# filter.net
KiCad netlist of a schematic drawn in EAGLE
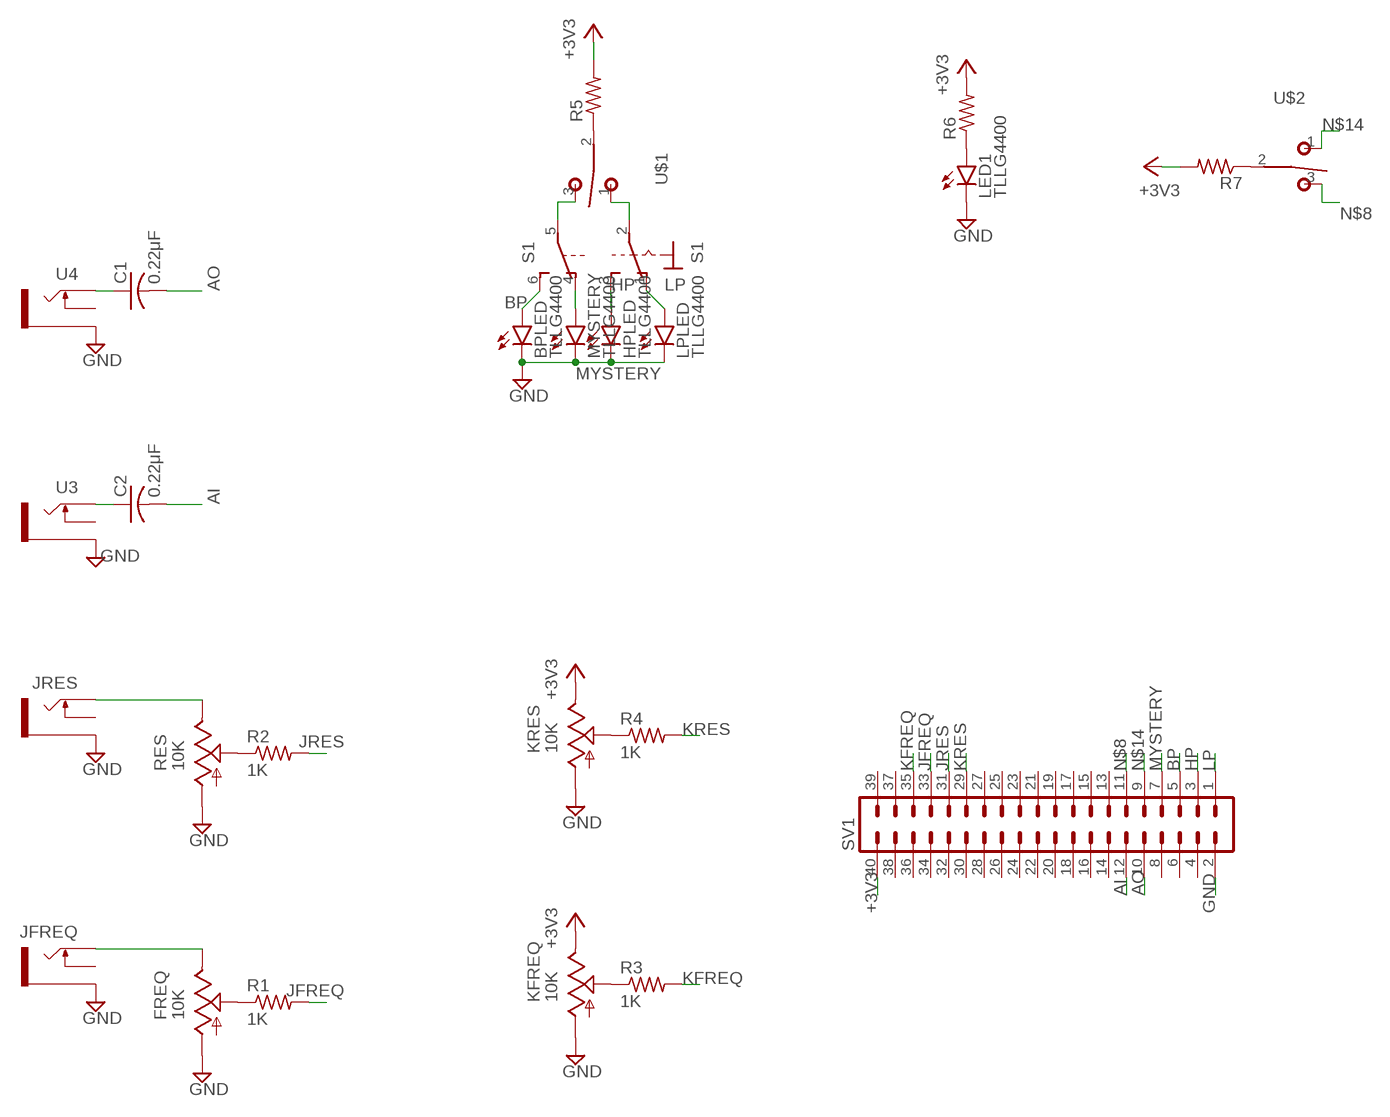
[diagram p0: schematic, sheet 1]

(export (version "E")
  (design (tool "Eeschema 10.0.6"))
  (components
    (comp (ref "BPLED")
      (value "TLLG4400")
      (footprint "eagle-import:LED3MM")
      (fields (field (name "MF") "VISHAY SEMICONDUCTOR"))
      (libsource (lib "eagle-import") (part "TLLG4400"))
    )
    (comp (ref "C1")
      (value "0.22μF")
      (footprint "eagle-import:C025-024X044")
      (libsource (lib "eagle-import") (part "C-US025-024X044"))
    )
    (comp (ref "C2")
      (value "0.22μF")
      (footprint "eagle-import:C025-024X044")
      (libsource (lib "eagle-import") (part "C-US025-024X044"))
    )
    (comp (ref "FREQ")
      (value "10K")
      (footprint "eagle-import:9MM_SNAP-IN_POT")
      (libsource (lib "eagle-import") (part "9MM_SNAP-IN_POT_"))
    )
    (comp (ref "HPLED")
      (value "TLLG4400")
      (footprint "eagle-import:LED3MM")
      (fields (field (name "MF") "VISHAY SEMICONDUCTOR"))
      (libsource (lib "eagle-import") (part "TLLG4400"))
    )
    (comp (ref "JFREQ")
      (value "THONKICONNNEW")
      (footprint "eagle-import:WQP-PJ301M-12_JACK")
      (libsource (lib "eagle-import") (part "THONKICONNNEW"))
    )
    (comp (ref "JRES")
      (value "THONKICONNNEW")
      (footprint "eagle-import:WQP-PJ301M-12_JACK")
      (libsource (lib "eagle-import") (part "THONKICONNNEW"))
    )
    (comp (ref "KFREQ")
      (value "10K")
      (footprint "eagle-import:9MM_SNAP-IN_POT")
      (libsource (lib "eagle-import") (part "9MM_SNAP-IN_POT_"))
    )
    (comp (ref "KRES")
      (value "10K")
      (footprint "eagle-import:9MM_SNAP-IN_POT")
      (libsource (lib "eagle-import") (part "9MM_SNAP-IN_POT_"))
    )
    (comp (ref "LED1")
      (value "TLLG4400")
      (footprint "eagle-import:LED3MM")
      (fields (field (name "MF") "VISHAY SEMICONDUCTOR"))
      (libsource (lib "eagle-import") (part "TLLG4400"))
    )
    (comp (ref "LPLED")
      (value "TLLG4400")
      (footprint "eagle-import:LED3MM")
      (fields (field (name "MF") "VISHAY SEMICONDUCTOR"))
      (libsource (lib "eagle-import") (part "TLLG4400"))
    )
    (comp (ref "MYSTERY")
      (value "TLLG4400")
      (footprint "eagle-import:LED3MM")
      (fields (field (name "MF") "VISHAY SEMICONDUCTOR"))
      (libsource (lib "eagle-import") (part "TLLG4400"))
    )
    (comp (ref "R1")
      (value "1K")
      (footprint "eagle-import:0207_10")
      (libsource (lib "eagle-import") (part "R-US_0207/10"))
    )
    (comp (ref "R2")
      (value "1K")
      (footprint "eagle-import:0207_10")
      (libsource (lib "eagle-import") (part "R-US_0207/10"))
    )
    (comp (ref "R3")
      (value "1K")
      (footprint "eagle-import:0207_10")
      (libsource (lib "eagle-import") (part "R-US_0207/10"))
    )
    (comp (ref "R4")
      (value "1K")
      (footprint "eagle-import:0207_10")
      (libsource (lib "eagle-import") (part "R-US_0207/10"))
    )
    (comp (ref "R5")
      (value "R-US_0207/10")
      (footprint "eagle-import:0207_10")
      (libsource (lib "eagle-import") (part "R-US_0207/10"))
    )
    (comp (ref "R6")
      (value "R-US_0207/10")
      (footprint "eagle-import:0207_10")
      (libsource (lib "eagle-import") (part "R-US_0207/10"))
    )
    (comp (ref "R7")
      (value "R-US_0207/10")
      (footprint "eagle-import:0207_10")
      (libsource (lib "eagle-import") (part "R-US_0207/10"))
    )
    (comp (ref "RES")
      (value "10K")
      (footprint "eagle-import:9MM_SNAP-IN_POT")
      (libsource (lib "eagle-import") (part "9MM_SNAP-IN_POT_"))
    )
    (comp (ref "S1")
      (value "320-938")
      (footprint "eagle-import:320-938")
      (libsource (lib "eagle-import") (part "320-938"))
    )
    (comp (ref "SV1")
      (value "MA20-2")
      (footprint "eagle-import:MA20-2")
      (libsource (lib "eagle-import") (part "MA20-2"))
    )
    (comp (ref "U$1")
      (value "T-80-T-SPDT-ON-OFF-ON")
      (footprint "eagle-import:M9040P")
      (libsource (lib "eagle-import") (part "T-80-T-SPDT-ON-OFF-ON"))
    )
    (comp (ref "U$2")
      (value "T-80-T-SPDT-ON-OFF-ON")
      (footprint "eagle-import:M9040P")
      (libsource (lib "eagle-import") (part "T-80-T-SPDT-ON-OFF-ON"))
    )
    (comp (ref "U3")
      (value "THONKICONNNEW")
      (footprint "eagle-import:WQP-PJ301M-12_JACK")
      (libsource (lib "eagle-import") (part "THONKICONNNEW"))
    )
    (comp (ref "U4")
      (value "THONKICONNNEW")
      (footprint "eagle-import:WQP-PJ301M-12_JACK")
      (libsource (lib "eagle-import") (part "THONKICONNNEW"))
    )
  )
  (nets
    (net (code "1") (name "+3V3") (class "Default")
      (node (ref "KFREQ") (pin "3") (pinfunction "E_3") (pintype "passive"))
      (node (ref "KRES") (pin "3") (pinfunction "E_3") (pintype "passive"))
      (node (ref "R5") (pin "2") (pinfunction "2_2") (pintype "passive"))
      (node (ref "R6") (pin "2") (pinfunction "2_2") (pintype "passive"))
      (node (ref "R7") (pin "2") (pinfunction "2_2") (pintype "passive"))
      (node (ref "SV1") (pin "40") (pinfunction "40_40") (pintype "passive"))
    )
    (net (code "2") (name "/AI") (class "Default")
      (node (ref "C2") (pin "2") (pinfunction "2_2") (pintype "passive"))
      (node (ref "SV1") (pin "12") (pinfunction "12_12") (pintype "passive"))
    )
    (net (code "3") (name "/AO") (class "Default")
      (node (ref "C1") (pin "2") (pinfunction "2_2") (pintype "passive"))
      (node (ref "SV1") (pin "10") (pinfunction "10_10") (pintype "passive"))
    )
    (net (code "4") (name "/BP") (class "Default")
      (node (ref "BPLED") (pin "A") (pinfunction "A_A") (pintype "passive"))
      (node (ref "S1") (pin "6") (pinfunction "S_6") (pintype "passive"))
      (node (ref "SV1") (pin "5") (pinfunction "5_5") (pintype "passive"))
    )
    (net (code "5") (name "/HP") (class "Default")
      (node (ref "HPLED") (pin "A") (pinfunction "A_A") (pintype "passive"))
      (node (ref "S1") (pin "3") (pinfunction "S_3") (pintype "passive"))
      (node (ref "SV1") (pin "3") (pinfunction "3_3") (pintype "passive"))
    )
    (net (code "6") (name "/JFREQ") (class "Default")
      (node (ref "R1") (pin "2") (pinfunction "2_2") (pintype "passive"))
      (node (ref "SV1") (pin "33") (pinfunction "33_33") (pintype "passive"))
    )
    (net (code "7") (name "/JRES") (class "Default")
      (node (ref "R2") (pin "2") (pinfunction "2_2") (pintype "passive"))
      (node (ref "SV1") (pin "31") (pinfunction "31_31") (pintype "passive"))
    )
    (net (code "8") (name "/KFREQ") (class "Default")
      (node (ref "R3") (pin "2") (pinfunction "2_2") (pintype "passive"))
      (node (ref "SV1") (pin "35") (pinfunction "35_35") (pintype "passive"))
    )
    (net (code "9") (name "/KRES") (class "Default")
      (node (ref "R4") (pin "2") (pinfunction "2_2") (pintype "passive"))
      (node (ref "SV1") (pin "29") (pinfunction "29_29") (pintype "passive"))
    )
    (net (code "10") (name "/LP") (class "Default")
      (node (ref "LPLED") (pin "A") (pinfunction "A_A") (pintype "passive"))
      (node (ref "S1") (pin "1") (pinfunction "O_1") (pintype "passive"))
      (node (ref "SV1") (pin "1") (pinfunction "1_1") (pintype "passive"))
    )
    (net (code "11") (name "/MYSTERY") (class "Default")
      (node (ref "MYSTERY") (pin "A") (pinfunction "A_A") (pintype "passive"))
      (node (ref "S1") (pin "4") (pinfunction "O_4") (pintype "passive"))
      (node (ref "SV1") (pin "7") (pinfunction "7_7") (pintype "passive"))
    )
    (net (code "12") (name "/N$8") (class "Default")
      (node (ref "SV1") (pin "11") (pinfunction "11_11") (pintype "passive"))
      (node (ref "U$2") (pin "3") (pinfunction "S_3") (pintype "passive"))
    )
    (net (code "13") (name "/N$14") (class "Default")
      (node (ref "SV1") (pin "9") (pinfunction "9_9") (pintype "passive"))
      (node (ref "U$2") (pin "1") (pinfunction "O_1") (pintype "passive"))
    )
    (net (code "14") (name "GND") (class "Default")
      (node (ref "BPLED") (pin "K") (pinfunction "C_K") (pintype "passive"))
      (node (ref "FREQ") (pin "1") (pinfunction "A_1") (pintype "passive"))
      (node (ref "HPLED") (pin "K") (pinfunction "C_K") (pintype "passive"))
      (node (ref "JFREQ") (pin "P$3_SLEEVE") (pinfunction "SLEEVE_P$3_SLEEVE") (pintype "passive"))
      (node (ref "JRES") (pin "P$3_SLEEVE") (pinfunction "SLEEVE_P$3_SLEEVE") (pintype "passive"))
      (node (ref "KFREQ") (pin "1") (pinfunction "A_1") (pintype "passive"))
      (node (ref "KRES") (pin "1") (pinfunction "A_1") (pintype "passive"))
      (node (ref "LED1") (pin "K") (pinfunction "C_K") (pintype "passive"))
      (node (ref "LPLED") (pin "K") (pinfunction "C_K") (pintype "passive"))
      (node (ref "MYSTERY") (pin "K") (pinfunction "C_K") (pintype "passive"))
      (node (ref "RES") (pin "1") (pinfunction "A_1") (pintype "passive"))
      (node (ref "SV1") (pin "2") (pinfunction "2_2") (pintype "passive"))
      (node (ref "U3") (pin "P$3_SLEEVE") (pinfunction "SLEEVE_P$3_SLEEVE") (pintype "passive"))
      (node (ref "U4") (pin "P$3_SLEEVE") (pinfunction "SLEEVE_P$3_SLEEVE") (pintype "passive"))
    )
    (net (code "15") (name "Net-(FREQ-E)") (class "Default")
      (node (ref "FREQ") (pin "3") (pinfunction "E_3") (pintype "passive"))
      (node (ref "JFREQ") (pin "P$1_TIP") (pinfunction "TIP_P$1_TIP") (pintype "passive"))
    )
    (net (code "16") (name "Net-(FREQ-S)") (class "Default")
      (node (ref "FREQ") (pin "2") (pinfunction "S_2") (pintype "passive"))
      (node (ref "R1") (pin "1") (pinfunction "1_1") (pintype "passive"))
    )
    (net (code "17") (name "Net-(JRES-TIP)") (class "Default")
      (node (ref "JRES") (pin "P$1_TIP") (pinfunction "TIP_P$1_TIP") (pintype "passive"))
      (node (ref "RES") (pin "3") (pinfunction "E_3") (pintype "passive"))
    )
    (net (code "18") (name "Net-(KFREQ-S)") (class "Default")
      (node (ref "KFREQ") (pin "2") (pinfunction "S_2") (pintype "passive"))
      (node (ref "R3") (pin "1") (pinfunction "1_1") (pintype "passive"))
    )
    (net (code "19") (name "Net-(KRES-S)") (class "Default")
      (node (ref "KRES") (pin "2") (pinfunction "S_2") (pintype "passive"))
      (node (ref "R4") (pin "1") (pinfunction "1_1") (pintype "passive"))
    )
    (net (code "20") (name "Net-(LED1-PadA)") (class "Default")
      (node (ref "LED1") (pin "A") (pinfunction "A_A") (pintype "passive"))
      (node (ref "R6") (pin "1") (pinfunction "1_1") (pintype "passive"))
    )
    (net (code "21") (name "Net-(RES-S)") (class "Default")
      (node (ref "R2") (pin "1") (pinfunction "1_1") (pintype "passive"))
      (node (ref "RES") (pin "2") (pinfunction "S_2") (pintype "passive"))
    )
    (net (code "22") (name "Net-(S1A-P)") (class "Default")
      (node (ref "S1") (pin "2") (pinfunction "P_2") (pintype "passive"))
      (node (ref "U$1") (pin "1") (pinfunction "O_1") (pintype "passive"))
    )
    (net (code "23") (name "Net-(S1B-P)") (class "Default")
      (node (ref "S1") (pin "5") (pinfunction "P_5") (pintype "passive"))
      (node (ref "U$1") (pin "3") (pinfunction "S_3") (pintype "passive"))
    )
    (net (code "24") (name "Net-(U$1-P)") (class "Default")
      (node (ref "R5") (pin "1") (pinfunction "1_1") (pintype "passive"))
      (node (ref "U$1") (pin "2") (pinfunction "P_2") (pintype "passive"))
    )
    (net (code "25") (name "Net-(U$2-P)") (class "Default")
      (node (ref "R7") (pin "1") (pinfunction "1_1") (pintype "passive"))
      (node (ref "U$2") (pin "2") (pinfunction "P_2") (pintype "passive"))
    )
    (net (code "26") (name "Net-(U3-TIP)") (class "Default")
      (node (ref "C2") (pin "1") (pinfunction "1_1") (pintype "passive"))
      (node (ref "U3") (pin "P$1_TIP") (pinfunction "TIP_P$1_TIP") (pintype "passive"))
    )
    (net (code "27") (name "Net-(U4-TIP)") (class "Default")
      (node (ref "C1") (pin "1") (pinfunction "1_1") (pintype "passive"))
      (node (ref "U4") (pin "P$1_TIP") (pinfunction "TIP_P$1_TIP") (pintype "passive"))
    )
    (net (code "28") (name "unconnected-(JFREQ-SWITCH-PadP$2_SWITCH)") (class "Default")
      (node (ref "JFREQ") (pin "P$2_SWITCH") (pinfunction "SWITCH_P$2_SWITCH") (pintype "passive"))
    )
    (net (code "29") (name "unconnected-(JRES-SWITCH-PadP$2_SWITCH)") (class "Default")
      (node (ref "JRES") (pin "P$2_SWITCH") (pinfunction "SWITCH_P$2_SWITCH") (pintype "passive"))
    )
    (net (code "30") (name "unconnected-(SV1-Pad4)") (class "Default")
      (node (ref "SV1") (pin "4") (pinfunction "4_4") (pintype "passive"))
    )
    (net (code "31") (name "unconnected-(SV1-Pad6)") (class "Default")
      (node (ref "SV1") (pin "6") (pinfunction "6_6") (pintype "passive"))
    )
    (net (code "32") (name "unconnected-(SV1-Pad8)") (class "Default")
      (node (ref "SV1") (pin "8") (pinfunction "8_8") (pintype "passive"))
    )
    (net (code "33") (name "unconnected-(SV1-Pad13)") (class "Default")
      (node (ref "SV1") (pin "13") (pinfunction "13_13") (pintype "passive"))
    )
    (net (code "34") (name "unconnected-(SV1-Pad14)") (class "Default")
      (node (ref "SV1") (pin "14") (pinfunction "14_14") (pintype "passive"))
    )
    (net (code "35") (name "unconnected-(SV1-Pad15)") (class "Default")
      (node (ref "SV1") (pin "15") (pinfunction "15_15") (pintype "passive"))
    )
    (net (code "36") (name "unconnected-(SV1-Pad16)") (class "Default")
      (node (ref "SV1") (pin "16") (pinfunction "16_16") (pintype "passive"))
    )
    (net (code "37") (name "unconnected-(SV1-Pad17)") (class "Default")
      (node (ref "SV1") (pin "17") (pinfunction "17_17") (pintype "passive"))
    )
    (net (code "38") (name "unconnected-(SV1-Pad18)") (class "Default")
      (node (ref "SV1") (pin "18") (pinfunction "18_18") (pintype "passive"))
    )
    (net (code "39") (name "unconnected-(SV1-Pad19)") (class "Default")
      (node (ref "SV1") (pin "19") (pinfunction "19_19") (pintype "passive"))
    )
    (net (code "40") (name "unconnected-(SV1-Pad20)") (class "Default")
      (node (ref "SV1") (pin "20") (pinfunction "20_20") (pintype "passive"))
    )
    (net (code "41") (name "unconnected-(SV1-Pad21)") (class "Default")
      (node (ref "SV1") (pin "21") (pinfunction "21_21") (pintype "passive"))
    )
    (net (code "42") (name "unconnected-(SV1-Pad22)") (class "Default")
      (node (ref "SV1") (pin "22") (pinfunction "22_22") (pintype "passive"))
    )
    (net (code "43") (name "unconnected-(SV1-Pad23)") (class "Default")
      (node (ref "SV1") (pin "23") (pinfunction "23_23") (pintype "passive"))
    )
    (net (code "44") (name "unconnected-(SV1-Pad24)") (class "Default")
      (node (ref "SV1") (pin "24") (pinfunction "24_24") (pintype "passive"))
    )
    (net (code "45") (name "unconnected-(SV1-Pad25)") (class "Default")
      (node (ref "SV1") (pin "25") (pinfunction "25_25") (pintype "passive"))
    )
    (net (code "46") (name "unconnected-(SV1-Pad26)") (class "Default")
      (node (ref "SV1") (pin "26") (pinfunction "26_26") (pintype "passive"))
    )
    (net (code "47") (name "unconnected-(SV1-Pad27)") (class "Default")
      (node (ref "SV1") (pin "27") (pinfunction "27_27") (pintype "passive"))
    )
    (net (code "48") (name "unconnected-(SV1-Pad28)") (class "Default")
      (node (ref "SV1") (pin "28") (pinfunction "28_28") (pintype "passive"))
    )
    (net (code "49") (name "unconnected-(SV1-Pad30)") (class "Default")
      (node (ref "SV1") (pin "30") (pinfunction "30_30") (pintype "passive"))
    )
    (net (code "50") (name "unconnected-(SV1-Pad32)") (class "Default")
      (node (ref "SV1") (pin "32") (pinfunction "32_32") (pintype "passive"))
    )
    (net (code "51") (name "unconnected-(SV1-Pad34)") (class "Default")
      (node (ref "SV1") (pin "34") (pinfunction "34_34") (pintype "passive"))
    )
    (net (code "52") (name "unconnected-(SV1-Pad36)") (class "Default")
      (node (ref "SV1") (pin "36") (pinfunction "36_36") (pintype "passive"))
    )
    (net (code "53") (name "unconnected-(SV1-Pad37)") (class "Default")
      (node (ref "SV1") (pin "37") (pinfunction "37_37") (pintype "passive"))
    )
    (net (code "54") (name "unconnected-(SV1-Pad38)") (class "Default")
      (node (ref "SV1") (pin "38") (pinfunction "38_38") (pintype "passive"))
    )
    (net (code "55") (name "unconnected-(SV1-Pad39)") (class "Default")
      (node (ref "SV1") (pin "39") (pinfunction "39_39") (pintype "passive"))
    )
    (net (code "56") (name "unconnected-(U3-SWITCH-PadP$2_SWITCH)") (class "Default")
      (node (ref "U3") (pin "P$2_SWITCH") (pinfunction "SWITCH_P$2_SWITCH") (pintype "passive"))
    )
    (net (code "57") (name "unconnected-(U4-SWITCH-PadP$2_SWITCH)") (class "Default")
      (node (ref "U4") (pin "P$2_SWITCH") (pinfunction "SWITCH_P$2_SWITCH") (pintype "passive"))
    )
  )
)
